# ZIGBEE.net
KiCad netlist of a schematic drawn in Altium Designer
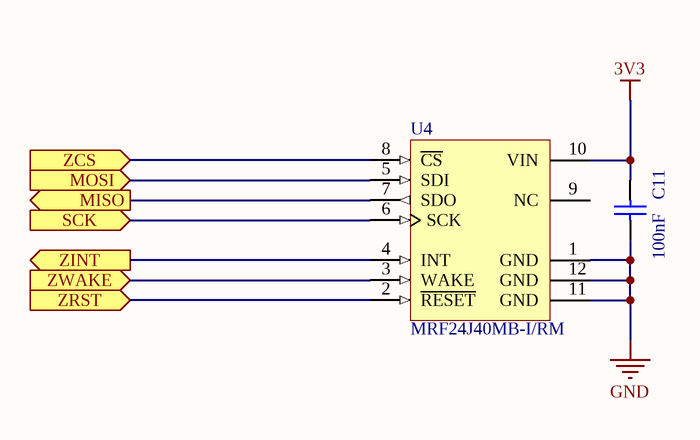
[diagram p0: ZIGBEE.SchDoc]

(export (version "E")
  (design (tool "Eeschema 10.0.6"))
  (components
    (comp (ref "C11")
      (value "100nF")
      (footprint "RESC2012L")
      (description "Capacitor (Semiconductor SIM Model)")
      (fields (field (name "Comment") "CAP0603-") (field (name "PUBLISHER") "Altium Limited"))
      (libsource (lib "Miscellaneous Devices") (part "Cap Semi"))
    )
    (comp (ref "U4")
      (value "MRF24J40MB-I/RM")
      (footprint "MRF24J40MB")
      (description "2.4 GHz IEEE Std. 802.15.4, 20 dBm RF Transceiver 12-Pin Module, Industrial Temperature")
      (fields (field (name "PUBLISHER") "Altium Limited"))
      (libsource (lib "Microchip Wireless Radio Frequency") (part "MRF24J40MB-I/RM"))
    )
  )
  (nets
    (net (code "1") (name "/MISO") (class "Default")
      (node (ref "U4") (pin "7") (pinfunction "SDO_7") (pintype "output"))
    )
    (net (code "2") (name "/MOSI") (class "Default")
      (node (ref "U4") (pin "5") (pinfunction "SDI_5") (pintype "input"))
    )
    (net (code "3") (name "/SCK") (class "Default")
      (node (ref "U4") (pin "6") (pinfunction "SCK_6") (pintype "input"))
    )
    (net (code "4") (name "/ZCS") (class "Default")
      (node (ref "U4") (pin "8") (pinfunction "~{CS}_8") (pintype "input"))
    )
    (net (code "5") (name "/ZINT") (class "Default")
      (node (ref "U4") (pin "4") (pinfunction "INT_4") (pintype "input"))
    )
    (net (code "6") (name "/ZRST") (class "Default")
      (node (ref "U4") (pin "2") (pinfunction "~{RESET}_2") (pintype "input"))
    )
    (net (code "7") (name "/ZWAKE") (class "Default")
      (node (ref "U4") (pin "3") (pinfunction "WAKE_3") (pintype "input"))
    )
    (net (code "8") (name "3V3") (class "Default")
      (node (ref "C11") (pin "2") (pinfunction "2_2") (pintype "passive"))
      (node (ref "U4") (pin "10") (pinfunction "VIN_10") (pintype "power_in"))
    )
    (net (code "9") (name "GND") (class "Default")
      (node (ref "C11") (pin "1") (pinfunction "1_1") (pintype "passive"))
      (node (ref "U4") (pin "1") (pinfunction "GND_1") (pintype "power_in"))
      (node (ref "U4") (pin "11") (pinfunction "GND_11") (pintype "power_in"))
      (node (ref "U4") (pin "12") (pinfunction "GND_12") (pintype "power_in"))
    )
    (net (code "10") (name "unconnected-(U4-NC-Pad9)") (class "Default")
      (node (ref "U4") (pin "9") (pinfunction "NC_9") (pintype "passive"))
    )
  )
)
